# powerboard.net
KiCad netlist of a schematic drawn in EAGLE
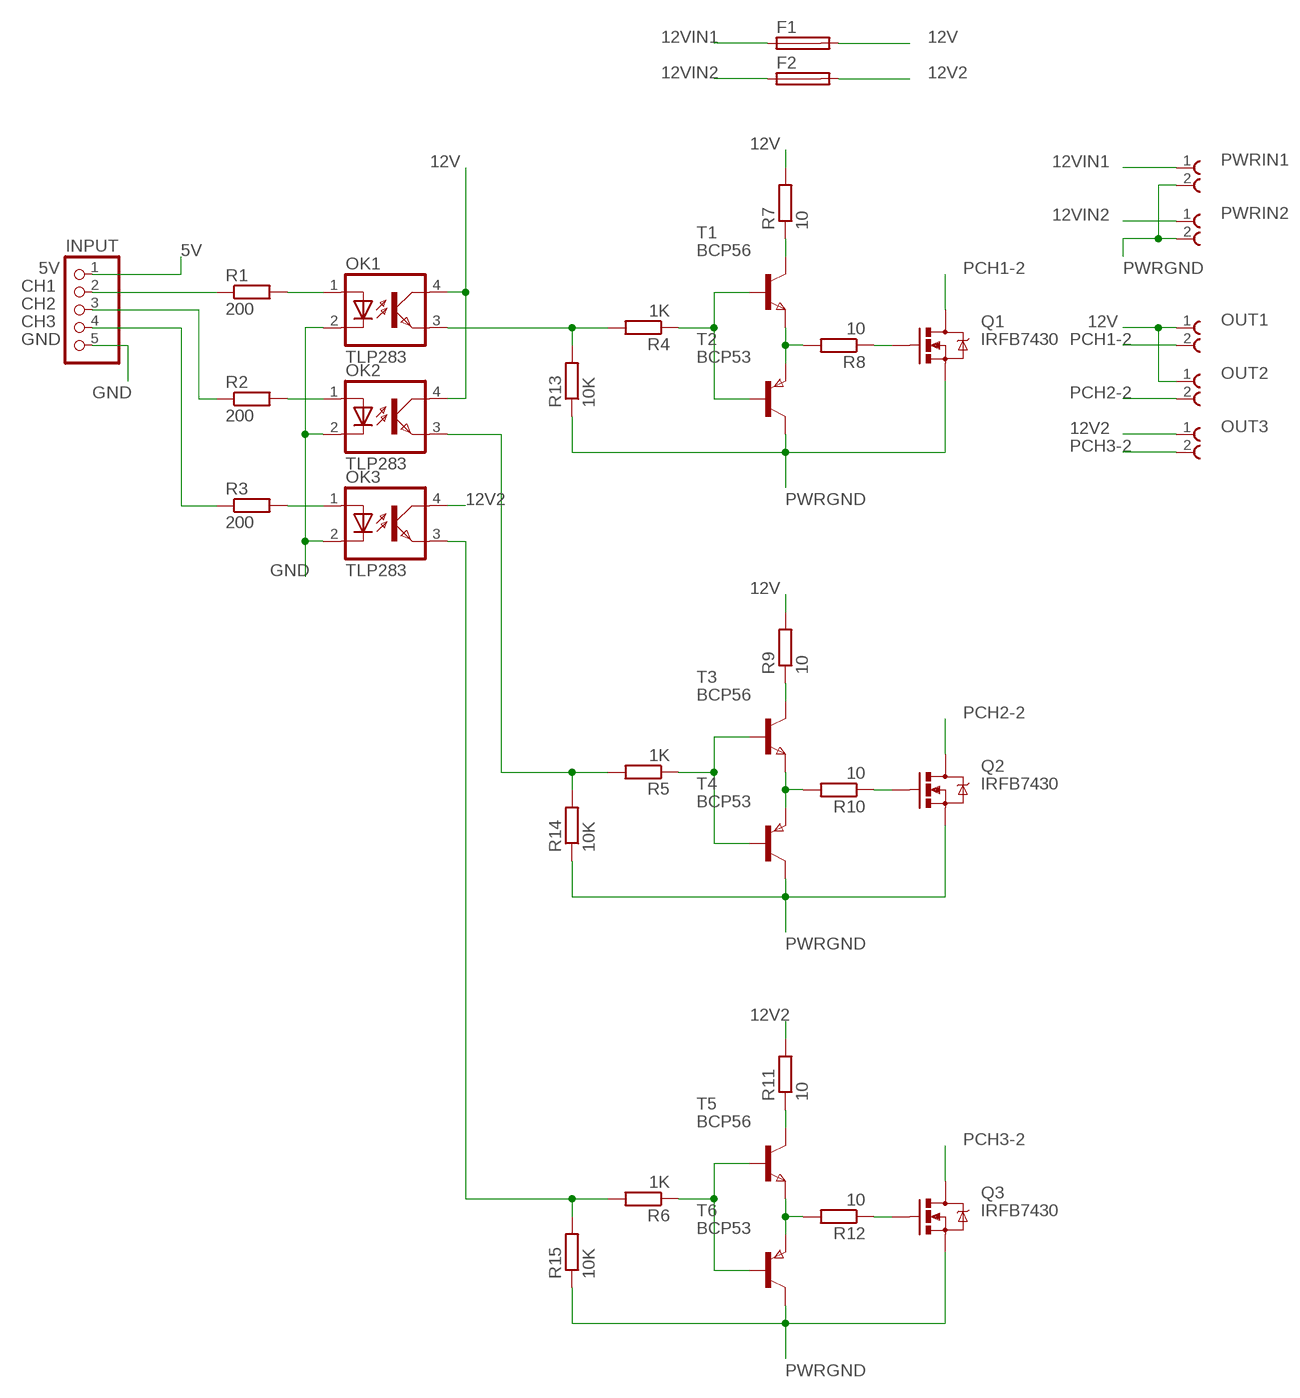
[diagram p0: schematic, sheet 1]

(export (version "E")
  (design (tool "Eeschema 10.0.6"))
  (components
    (comp (ref "F1")
      (value "SH22,5")
      (footprint "eagle-import:SH22,5")
      (fields (field (name "MF") "SCHURTER") (field (name "MPN") "0031.8201"))
      (libsource (lib "eagle-import") (part "SH22,5"))
    )
    (comp (ref "F2")
      (value "SH22,5")
      (footprint "eagle-import:SH22,5")
      (fields (field (name "MF") "SCHURTER") (field (name "MPN") "0031.8201"))
      (libsource (lib "eagle-import") (part "SH22,5"))
    )
    (comp (ref "INPUT")
      (value "PINHD-1X5")
      (footprint "eagle-import:1X05")
      (libsource (lib "eagle-import") (part "PINHD-1X5"))
    )
    (comp (ref "OK1")
      (value "TLP283")
      (footprint "eagle-import:MINI-FLAT-4")
      (libsource (lib "eagle-import") (part "TLP283"))
    )
    (comp (ref "OK2")
      (value "TLP283")
      (footprint "eagle-import:MINI-FLAT-4")
      (libsource (lib "eagle-import") (part "TLP283"))
    )
    (comp (ref "OK3")
      (value "TLP283")
      (footprint "eagle-import:MINI-FLAT-4")
      (libsource (lib "eagle-import") (part "TLP283"))
    )
    (comp (ref "OUT1")
      (value "691244610002")
      (footprint "eagle-import:691244610002")
      (libsource (lib "eagle-import") (part "691244610002"))
    )
    (comp (ref "OUT2")
      (value "691244610002")
      (footprint "eagle-import:691244610002")
      (libsource (lib "eagle-import") (part "691244610002"))
    )
    (comp (ref "OUT3")
      (value "691244610002")
      (footprint "eagle-import:691244610002")
      (libsource (lib "eagle-import") (part "691244610002"))
    )
    (comp (ref "PWRIN1")
      (value "691244610002")
      (footprint "eagle-import:691244610002")
      (libsource (lib "eagle-import") (part "691244610002"))
    )
    (comp (ref "PWRIN2")
      (value "691244610002")
      (footprint "eagle-import:691244610002")
      (libsource (lib "eagle-import") (part "691244610002"))
    )
    (comp (ref "Q1")
      (value "IRFB7430")
      (footprint "eagle-import:TO220V")
      (libsource (lib "eagle-import") (part "MOSFET-NCHANNELFQP30N06L"))
    )
    (comp (ref "Q2")
      (value "IRFB7430")
      (footprint "eagle-import:TO220V")
      (libsource (lib "eagle-import") (part "MOSFET-NCHANNELFQP30N06L"))
    )
    (comp (ref "Q3")
      (value "IRFB7430")
      (footprint "eagle-import:TO220V")
      (libsource (lib "eagle-import") (part "MOSFET-NCHANNELFQP30N06L"))
    )
    (comp (ref "R1")
      (value "200")
      (footprint "eagle-import:R0805")
      (libsource (lib "eagle-import") (part "R-EU_R0805"))
    )
    (comp (ref "R2")
      (value "200")
      (footprint "eagle-import:R0805")
      (libsource (lib "eagle-import") (part "R-EU_R0805"))
    )
    (comp (ref "R3")
      (value "200")
      (footprint "eagle-import:R0805")
      (libsource (lib "eagle-import") (part "R-EU_R0805"))
    )
    (comp (ref "R4")
      (value "1K")
      (footprint "eagle-import:R0805")
      (libsource (lib "eagle-import") (part "R-EU_R0805"))
    )
    (comp (ref "R5")
      (value "1K")
      (footprint "eagle-import:R0805")
      (libsource (lib "eagle-import") (part "R-EU_R0805"))
    )
    (comp (ref "R6")
      (value "1K")
      (footprint "eagle-import:R0805")
      (libsource (lib "eagle-import") (part "R-EU_R0805"))
    )
    (comp (ref "R7")
      (value "10")
      (footprint "eagle-import:R0805")
      (libsource (lib "eagle-import") (part "R-EU_R0805"))
    )
    (comp (ref "R8")
      (value "10")
      (footprint "eagle-import:R0805")
      (libsource (lib "eagle-import") (part "R-EU_R0805"))
    )
    (comp (ref "R9")
      (value "10")
      (footprint "eagle-import:R0805")
      (libsource (lib "eagle-import") (part "R-EU_R0805"))
    )
    (comp (ref "R10")
      (value "10")
      (footprint "eagle-import:R0805")
      (libsource (lib "eagle-import") (part "R-EU_R0805"))
    )
    (comp (ref "R11")
      (value "10")
      (footprint "eagle-import:R0805")
      (libsource (lib "eagle-import") (part "R-EU_R0805"))
    )
    (comp (ref "R12")
      (value "10")
      (footprint "eagle-import:R0805")
      (libsource (lib "eagle-import") (part "R-EU_R0805"))
    )
    (comp (ref "R13")
      (value "10K")
      (footprint "eagle-import:R0805")
      (libsource (lib "eagle-import") (part "R-EU_R0805"))
    )
    (comp (ref "R14")
      (value "10K")
      (footprint "eagle-import:R0805")
      (libsource (lib "eagle-import") (part "R-EU_R0805"))
    )
    (comp (ref "R15")
      (value "10K")
      (footprint "eagle-import:R0805")
      (libsource (lib "eagle-import") (part "R-EU_R0805"))
    )
    (comp (ref "T1")
      (value "BCP56")
      (footprint "eagle-import:SOT223")
      (fields (field (name "MPN") "DJT4031N-13"))
      (libsource (lib "eagle-import") (part "NPNSOT223"))
    )
    (comp (ref "T2")
      (value "BCP53")
      (footprint "eagle-import:SOT223")
      (fields (field (name "MPN") "DJT4030P-13"))
      (libsource (lib "eagle-import") (part "PNPSOT223"))
    )
    (comp (ref "T3")
      (value "BCP56")
      (footprint "eagle-import:SOT223")
      (fields (field (name "MPN") "DJT4031N-13"))
      (libsource (lib "eagle-import") (part "NPNSOT223"))
    )
    (comp (ref "T4")
      (value "BCP53")
      (footprint "eagle-import:SOT223")
      (fields (field (name "MPN") "DJT4030P-13"))
      (libsource (lib "eagle-import") (part "PNPSOT223"))
    )
    (comp (ref "T5")
      (value "BCP56")
      (footprint "eagle-import:SOT223")
      (fields (field (name "MPN") "DJT4031N-13"))
      (libsource (lib "eagle-import") (part "NPNSOT223"))
    )
    (comp (ref "T6")
      (value "BCP53")
      (footprint "eagle-import:SOT223")
      (fields (field (name "MPN") "DJT4030P-13"))
      (libsource (lib "eagle-import") (part "PNPSOT223"))
    )
  )
  (nets
    (net (code "1") (name "/5V") (class "Default")
      (node (ref "INPUT") (pin "1") (pinfunction "1_1") (pintype "passive"))
    )
    (net (code "2") (name "/12V") (class "Default")
      (node (ref "F1") (pin "2") (pinfunction "2_2") (pintype "passive"))
      (node (ref "OK1") (pin "4") (pinfunction "COL_4") (pintype "passive"))
      (node (ref "OK2") (pin "4") (pinfunction "COL_4") (pintype "passive"))
      (node (ref "OUT1") (pin "1") (pinfunction "1_1") (pintype "passive"))
      (node (ref "OUT2") (pin "1") (pinfunction "1_1") (pintype "passive"))
      (node (ref "R7") (pin "2") (pinfunction "2_2") (pintype "passive"))
      (node (ref "R9") (pin "2") (pinfunction "2_2") (pintype "passive"))
    )
    (net (code "3") (name "/12V2") (class "Default")
      (node (ref "F2") (pin "2") (pinfunction "2_2") (pintype "passive"))
      (node (ref "OK3") (pin "4") (pinfunction "COL_4") (pintype "passive"))
      (node (ref "OUT3") (pin "1") (pinfunction "1_1") (pintype "passive"))
      (node (ref "R11") (pin "2") (pinfunction "2_2") (pintype "passive"))
    )
    (net (code "4") (name "/12VIN1") (class "Default")
      (node (ref "F1") (pin "1") (pinfunction "1_1") (pintype "passive"))
      (node (ref "PWRIN1") (pin "1") (pinfunction "1_1") (pintype "passive"))
    )
    (net (code "5") (name "/12VIN2") (class "Default")
      (node (ref "F2") (pin "1") (pinfunction "1_1") (pintype "passive"))
      (node (ref "PWRIN2") (pin "1") (pinfunction "1_1") (pintype "passive"))
    )
    (net (code "6") (name "/CH1") (class "Default")
      (node (ref "INPUT") (pin "2") (pinfunction "2_2") (pintype "passive"))
      (node (ref "R1") (pin "1") (pinfunction "1_1") (pintype "passive"))
    )
    (net (code "7") (name "/CH2") (class "Default")
      (node (ref "INPUT") (pin "3") (pinfunction "3_3") (pintype "passive"))
      (node (ref "R2") (pin "1") (pinfunction "1_1") (pintype "passive"))
    )
    (net (code "8") (name "/CH3") (class "Default")
      (node (ref "INPUT") (pin "4") (pinfunction "4_4") (pintype "passive"))
      (node (ref "R3") (pin "1") (pinfunction "1_1") (pintype "passive"))
    )
    (net (code "9") (name "/GND") (class "Default")
      (node (ref "INPUT") (pin "5") (pinfunction "5_5") (pintype "passive"))
      (node (ref "OK1") (pin "2") (pinfunction "C_2") (pintype "passive"))
      (node (ref "OK2") (pin "2") (pinfunction "C_2") (pintype "passive"))
      (node (ref "OK3") (pin "2") (pinfunction "C_2") (pintype "passive"))
    )
    (net (code "10") (name "/PCH1-2") (class "Default")
      (node (ref "OUT1") (pin "2") (pinfunction "2_2") (pintype "passive"))
      (node (ref "Q1") (pin "2") (pinfunction "D_2") (pintype "passive"))
    )
    (net (code "11") (name "/PCH2-2") (class "Default")
      (node (ref "OUT2") (pin "2") (pinfunction "2_2") (pintype "passive"))
      (node (ref "Q2") (pin "2") (pinfunction "D_2") (pintype "passive"))
    )
    (net (code "12") (name "/PCH3-2") (class "Default")
      (node (ref "OUT3") (pin "2") (pinfunction "2_2") (pintype "passive"))
      (node (ref "Q3") (pin "2") (pinfunction "D_2") (pintype "passive"))
    )
    (net (code "13") (name "/PWRGND") (class "Default")
      (node (ref "PWRIN1") (pin "2") (pinfunction "2_2") (pintype "passive"))
      (node (ref "PWRIN2") (pin "2") (pinfunction "2_2") (pintype "passive"))
      (node (ref "Q1") (pin "3") (pinfunction "S_3") (pintype "passive"))
      (node (ref "Q2") (pin "3") (pinfunction "S_3") (pintype "passive"))
      (node (ref "Q3") (pin "3") (pinfunction "S_3") (pintype "passive"))
      (node (ref "R13") (pin "1") (pinfunction "1_1") (pintype "passive"))
      (node (ref "R14") (pin "1") (pinfunction "1_1") (pintype "passive"))
      (node (ref "R15") (pin "1") (pinfunction "1_1") (pintype "passive"))
      (node (ref "T2") (pin "2") (pinfunction "C_2") (pintype "passive"))
      (node (ref "T2") (pin "4") (pinfunction "C_4") (pintype "passive"))
      (node (ref "T4") (pin "2") (pinfunction "C_2") (pintype "passive"))
      (node (ref "T4") (pin "4") (pinfunction "C_4") (pintype "passive"))
      (node (ref "T6") (pin "2") (pinfunction "C_2") (pintype "passive"))
      (node (ref "T6") (pin "4") (pinfunction "C_4") (pintype "passive"))
    )
    (net (code "14") (name "Net-(OK1-A)") (class "Default")
      (node (ref "OK1") (pin "1") (pinfunction "A_1") (pintype "passive"))
      (node (ref "R1") (pin "2") (pinfunction "2_2") (pintype "passive"))
    )
    (net (code "15") (name "Net-(OK1-EMIT)") (class "Default")
      (node (ref "OK1") (pin "3") (pinfunction "EMIT_3") (pintype "passive"))
      (node (ref "R13") (pin "2") (pinfunction "2_2") (pintype "passive"))
      (node (ref "R4") (pin "2") (pinfunction "2_2") (pintype "passive"))
    )
    (net (code "16") (name "Net-(OK2-A)") (class "Default")
      (node (ref "OK2") (pin "1") (pinfunction "A_1") (pintype "passive"))
      (node (ref "R2") (pin "2") (pinfunction "2_2") (pintype "passive"))
    )
    (net (code "17") (name "Net-(OK2-EMIT)") (class "Default")
      (node (ref "OK2") (pin "3") (pinfunction "EMIT_3") (pintype "passive"))
      (node (ref "R14") (pin "2") (pinfunction "2_2") (pintype "passive"))
      (node (ref "R5") (pin "2") (pinfunction "2_2") (pintype "passive"))
    )
    (net (code "18") (name "Net-(OK3-A)") (class "Default")
      (node (ref "OK3") (pin "1") (pinfunction "A_1") (pintype "passive"))
      (node (ref "R3") (pin "2") (pinfunction "2_2") (pintype "passive"))
    )
    (net (code "19") (name "Net-(OK3-EMIT)") (class "Default")
      (node (ref "OK3") (pin "3") (pinfunction "EMIT_3") (pintype "passive"))
      (node (ref "R15") (pin "2") (pinfunction "2_2") (pintype "passive"))
      (node (ref "R6") (pin "2") (pinfunction "2_2") (pintype "passive"))
    )
    (net (code "20") (name "Net-(Q1-G)") (class "Default")
      (node (ref "Q1") (pin "1") (pinfunction "G_1") (pintype "passive"))
      (node (ref "R8") (pin "1") (pinfunction "1_1") (pintype "passive"))
    )
    (net (code "21") (name "Net-(Q2-G)") (class "Default")
      (node (ref "Q2") (pin "1") (pinfunction "G_1") (pintype "passive"))
      (node (ref "R10") (pin "1") (pinfunction "1_1") (pintype "passive"))
    )
    (net (code "22") (name "Net-(Q3-G)") (class "Default")
      (node (ref "Q3") (pin "1") (pinfunction "G_1") (pintype "passive"))
      (node (ref "R12") (pin "1") (pinfunction "1_1") (pintype "passive"))
    )
    (net (code "23") (name "Net-(R7-Pad1)") (class "Default")
      (node (ref "R7") (pin "1") (pinfunction "1_1") (pintype "passive"))
      (node (ref "T1") (pin "2") (pinfunction "C_2") (pintype "passive"))
      (node (ref "T1") (pin "4") (pinfunction "C_4") (pintype "passive"))
    )
    (net (code "24") (name "Net-(R9-Pad1)") (class "Default")
      (node (ref "R9") (pin "1") (pinfunction "1_1") (pintype "passive"))
      (node (ref "T3") (pin "2") (pinfunction "C_2") (pintype "passive"))
      (node (ref "T3") (pin "4") (pinfunction "C_4") (pintype "passive"))
    )
    (net (code "25") (name "Net-(R11-Pad1)") (class "Default")
      (node (ref "R11") (pin "1") (pinfunction "1_1") (pintype "passive"))
      (node (ref "T5") (pin "2") (pinfunction "C_2") (pintype "passive"))
      (node (ref "T5") (pin "4") (pinfunction "C_4") (pintype "passive"))
    )
    (net (code "26") (name "Net-(T1-B)") (class "Default")
      (node (ref "R4") (pin "1") (pinfunction "1_1") (pintype "passive"))
      (node (ref "T1") (pin "1") (pinfunction "B_1") (pintype "passive"))
      (node (ref "T2") (pin "1") (pinfunction "B_1") (pintype "passive"))
    )
    (net (code "27") (name "Net-(T1-E)") (class "Default")
      (node (ref "R8") (pin "2") (pinfunction "2_2") (pintype "passive"))
      (node (ref "T1") (pin "3") (pinfunction "E_3") (pintype "passive"))
      (node (ref "T2") (pin "3") (pinfunction "E_3") (pintype "passive"))
    )
    (net (code "28") (name "Net-(T3-B)") (class "Default")
      (node (ref "R5") (pin "1") (pinfunction "1_1") (pintype "passive"))
      (node (ref "T3") (pin "1") (pinfunction "B_1") (pintype "passive"))
      (node (ref "T4") (pin "1") (pinfunction "B_1") (pintype "passive"))
    )
    (net (code "29") (name "Net-(T3-E)") (class "Default")
      (node (ref "R10") (pin "2") (pinfunction "2_2") (pintype "passive"))
      (node (ref "T3") (pin "3") (pinfunction "E_3") (pintype "passive"))
      (node (ref "T4") (pin "3") (pinfunction "E_3") (pintype "passive"))
    )
    (net (code "30") (name "Net-(T5-B)") (class "Default")
      (node (ref "R6") (pin "1") (pinfunction "1_1") (pintype "passive"))
      (node (ref "T5") (pin "1") (pinfunction "B_1") (pintype "passive"))
      (node (ref "T6") (pin "1") (pinfunction "B_1") (pintype "passive"))
    )
    (net (code "31") (name "Net-(T5-E)") (class "Default")
      (node (ref "R12") (pin "2") (pinfunction "2_2") (pintype "passive"))
      (node (ref "T5") (pin "3") (pinfunction "E_3") (pintype "passive"))
      (node (ref "T6") (pin "3") (pinfunction "E_3") (pintype "passive"))
    )
  )
)
